# Esquema.net
KiCad netlist of a schematic drawn in EAGLE
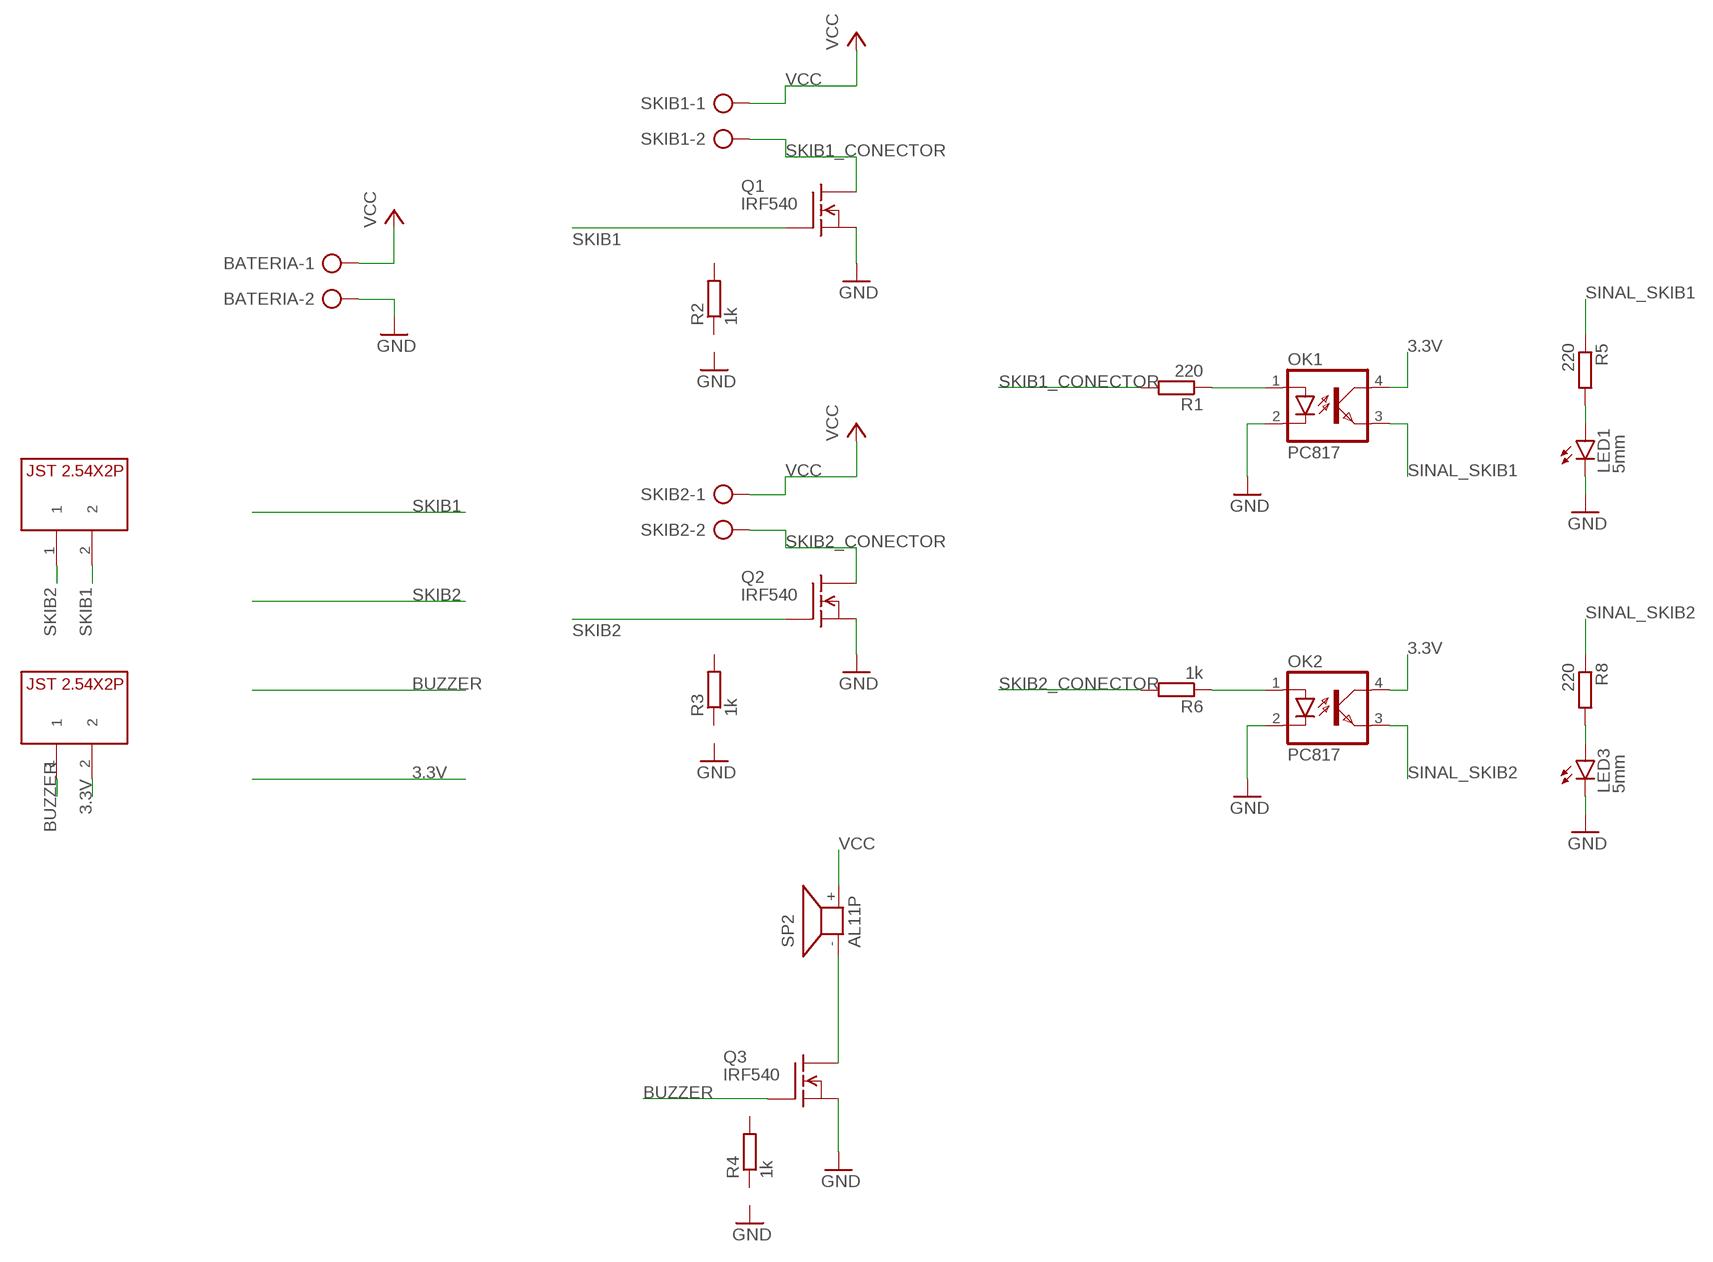
[diagram p0: schematic, sheet 1]

(export (version "E")
  (design (tool "Eeschema 10.0.6"))
  (components
    (comp (ref "BATERIA")
      (value "AK500/2-H")
      (footprint "eagle-import:AK500_2-H")
      (libsource (lib "eagle-import") (part "AK500/2-H"))
    )
    (comp (ref "LED1")
      (value "5mm")
      (footprint "eagle-import:LED5MM")
      (libsource (lib "eagle-import") (part "LED5MM"))
    )
    (comp (ref "LED3")
      (value "5mm")
      (footprint "eagle-import:LED5MM")
      (libsource (lib "eagle-import") (part "LED5MM"))
    )
    (comp (ref "OK1")
      (value "PC817")
      (footprint "eagle-import:DIL04")
      (fields (field (name "MPN") "PC817X4J000F"))
      (libsource (lib "eagle-import") (part "PC817"))
    )
    (comp (ref "OK2")
      (value "PC817")
      (footprint "eagle-import:DIL04")
      (fields (field (name "MPN") "PC817X4J000F"))
      (libsource (lib "eagle-import") (part "PC817"))
    )
    (comp (ref "Q1")
      (value "IRF540")
      (footprint "eagle-import:TO220")
      (libsource (lib "eagle-import") (part "IRF540"))
    )
    (comp (ref "Q2")
      (value "IRF540")
      (footprint "eagle-import:TO220")
      (libsource (lib "eagle-import") (part "IRF540"))
    )
    (comp (ref "Q3")
      (value "IRF540")
      (footprint "eagle-import:TO220")
      (libsource (lib "eagle-import") (part "IRF540"))
    )
    (comp (ref "R1")
      (value "220")
      (footprint "eagle-import:0207_10")
      (libsource (lib "eagle-import") (part "R-EU_0207/10"))
    )
    (comp (ref "R2")
      (value "1k")
      (footprint "eagle-import:0207_10")
      (libsource (lib "eagle-import") (part "R-EU_0207/10"))
    )
    (comp (ref "R3")
      (value "1k")
      (footprint "eagle-import:0207_10")
      (libsource (lib "eagle-import") (part "R-EU_0207/10"))
    )
    (comp (ref "R4")
      (value "1k")
      (footprint "eagle-import:0207_10")
      (libsource (lib "eagle-import") (part "R-EU_0207/10"))
    )
    (comp (ref "R5")
      (value "220")
      (footprint "eagle-import:0207_10")
      (libsource (lib "eagle-import") (part "R-EU_0207/10"))
    )
    (comp (ref "R6")
      (value "1k")
      (footprint "eagle-import:0207_10")
      (libsource (lib "eagle-import") (part "R-EU_0207/10"))
    )
    (comp (ref "R8")
      (value "220")
      (footprint "eagle-import:0207_10")
      (libsource (lib "eagle-import") (part "R-EU_0207/10"))
    )
    (comp (ref "SKIB1")
      (value "AK500/2-H")
      (footprint "eagle-import:AK500_2-H")
      (libsource (lib "eagle-import") (part "AK500/2-H"))
    )
    (comp (ref "SKIB2")
      (value "AK500/2-H")
      (footprint "eagle-import:AK500_2-H")
      (libsource (lib "eagle-import") (part "AK500/2-H"))
    )
    (comp (ref "SP2")
      (value "AL11P")
      (footprint "eagle-import:AL11P")
      (libsource (lib "eagle-import") (part "AL11P"))
    )
    (comp (ref "U$1")
      (value "JST2.54X2P")
      (footprint "eagle-import:JST2.54X2P_FOOTPRINT")
      (libsource (lib "eagle-import") (part "JST2.54X2P"))
    )
    (comp (ref "U$2")
      (value "JST2.54X2P")
      (footprint "eagle-import:JST2.54X2P_FOOTPRINT")
      (libsource (lib "eagle-import") (part "JST2.54X2P"))
    )
  )
  (nets
    (net (code "1") (name "/3.3V") (class "Default")
      (node (ref "OK1") (pin "4") (pinfunction "COL_4") (pintype "passive"))
      (node (ref "OK2") (pin "4") (pinfunction "COL_4") (pintype "passive"))
      (node (ref "U$1") (pin "2") (pinfunction "2_2") (pintype "bidirectional"))
    )
    (net (code "2") (name "/BUZZER") (class "Default")
      (node (ref "Q3") (pin "1") (pinfunction "G_1") (pintype "passive"))
      (node (ref "U$1") (pin "1") (pinfunction "1_1") (pintype "bidirectional"))
    )
    (net (code "3") (name "/SINAL_SKIB1") (class "Default")
      (node (ref "OK1") (pin "3") (pinfunction "EMIT_3") (pintype "passive"))
      (node (ref "R5") (pin "1") (pinfunction "1_1") (pintype "passive"))
    )
    (net (code "4") (name "/SINAL_SKIB2") (class "Default")
      (node (ref "OK2") (pin "3") (pinfunction "EMIT_3") (pintype "passive"))
      (node (ref "R8") (pin "1") (pinfunction "1_1") (pintype "passive"))
    )
    (net (code "5") (name "/SKIB1") (class "Default")
      (node (ref "Q1") (pin "1") (pinfunction "G_1") (pintype "passive"))
      (node (ref "U$2") (pin "2") (pinfunction "2_2") (pintype "bidirectional"))
    )
    (net (code "6") (name "/SKIB1_CONECTOR") (class "Default")
      (node (ref "Q1") (pin "2") (pinfunction "D_2") (pintype "passive"))
      (node (ref "R1") (pin "2") (pinfunction "2_2") (pintype "passive"))
      (node (ref "SKIB1") (pin "2") (pinfunction "KL_2") (pintype "passive"))
    )
    (net (code "7") (name "/SKIB2") (class "Default")
      (node (ref "Q2") (pin "1") (pinfunction "G_1") (pintype "passive"))
      (node (ref "U$2") (pin "1") (pinfunction "1_1") (pintype "bidirectional"))
    )
    (net (code "8") (name "/SKIB2_CONECTOR") (class "Default")
      (node (ref "Q2") (pin "2") (pinfunction "D_2") (pintype "passive"))
      (node (ref "R6") (pin "2") (pinfunction "2_2") (pintype "passive"))
      (node (ref "SKIB2") (pin "2") (pinfunction "KL_2") (pintype "passive"))
    )
    (net (code "9") (name "GND") (class "Default")
      (node (ref "BATERIA") (pin "2") (pinfunction "KL_2") (pintype "passive"))
      (node (ref "LED1") (pin "K") (pinfunction "C_K") (pintype "passive"))
      (node (ref "LED3") (pin "K") (pinfunction "C_K") (pintype "passive"))
      (node (ref "OK1") (pin "2") (pinfunction "C_2") (pintype "passive"))
      (node (ref "OK2") (pin "2") (pinfunction "C_2") (pintype "passive"))
      (node (ref "Q1") (pin "3") (pinfunction "S_3") (pintype "passive"))
      (node (ref "Q2") (pin "3") (pinfunction "S_3") (pintype "passive"))
      (node (ref "Q3") (pin "3") (pinfunction "S_3") (pintype "passive"))
    )
    (net (code "10") (name "Net-(LED1-PadA)") (class "Default")
      (node (ref "LED1") (pin "A") (pinfunction "A_A") (pintype "passive"))
      (node (ref "R5") (pin "2") (pinfunction "2_2") (pintype "passive"))
    )
    (net (code "11") (name "Net-(LED3-PadA)") (class "Default")
      (node (ref "LED3") (pin "A") (pinfunction "A_A") (pintype "passive"))
      (node (ref "R8") (pin "2") (pinfunction "2_2") (pintype "passive"))
    )
    (net (code "12") (name "Net-(OK1-A)") (class "Default")
      (node (ref "OK1") (pin "1") (pinfunction "A_1") (pintype "passive"))
      (node (ref "R1") (pin "1") (pinfunction "1_1") (pintype "passive"))
    )
    (net (code "13") (name "Net-(OK2-A)") (class "Default")
      (node (ref "OK2") (pin "1") (pinfunction "A_1") (pintype "passive"))
      (node (ref "R6") (pin "1") (pinfunction "1_1") (pintype "passive"))
    )
    (net (code "14") (name "Net-(Q3-D)") (class "Default")
      (node (ref "Q3") (pin "2") (pinfunction "D_2") (pintype "passive"))
      (node (ref "SP2") (pin "-") (pinfunction "1_-") (pintype "passive"))
    )
    (net (code "15") (name "VCC") (class "Default")
      (node (ref "BATERIA") (pin "1") (pinfunction "KL_1") (pintype "passive"))
      (node (ref "SKIB1") (pin "1") (pinfunction "KL_1") (pintype "passive"))
      (node (ref "SKIB2") (pin "1") (pinfunction "KL_1") (pintype "passive"))
      (node (ref "SP2") (pin "+") (pinfunction "2_+") (pintype "passive"))
    )
    (net (code "16") (name "unconnected-(R2-Pad1)") (class "Default")
      (node (ref "R2") (pin "1") (pinfunction "1_1") (pintype "passive"))
    )
    (net (code "17") (name "unconnected-(R2-Pad2)") (class "Default")
      (node (ref "R2") (pin "2") (pinfunction "2_2") (pintype "passive"))
    )
    (net (code "18") (name "unconnected-(R3-Pad1)") (class "Default")
      (node (ref "R3") (pin "1") (pinfunction "1_1") (pintype "passive"))
    )
    (net (code "19") (name "unconnected-(R3-Pad2)") (class "Default")
      (node (ref "R3") (pin "2") (pinfunction "2_2") (pintype "passive"))
    )
    (net (code "20") (name "unconnected-(R4-Pad1)") (class "Default")
      (node (ref "R4") (pin "1") (pinfunction "1_1") (pintype "passive"))
    )
    (net (code "21") (name "unconnected-(R4-Pad2)") (class "Default")
      (node (ref "R4") (pin "2") (pinfunction "2_2") (pintype "passive"))
    )
  )
)
